# V3.net
KiCad netlist of a schematic drawn in Altium Designer
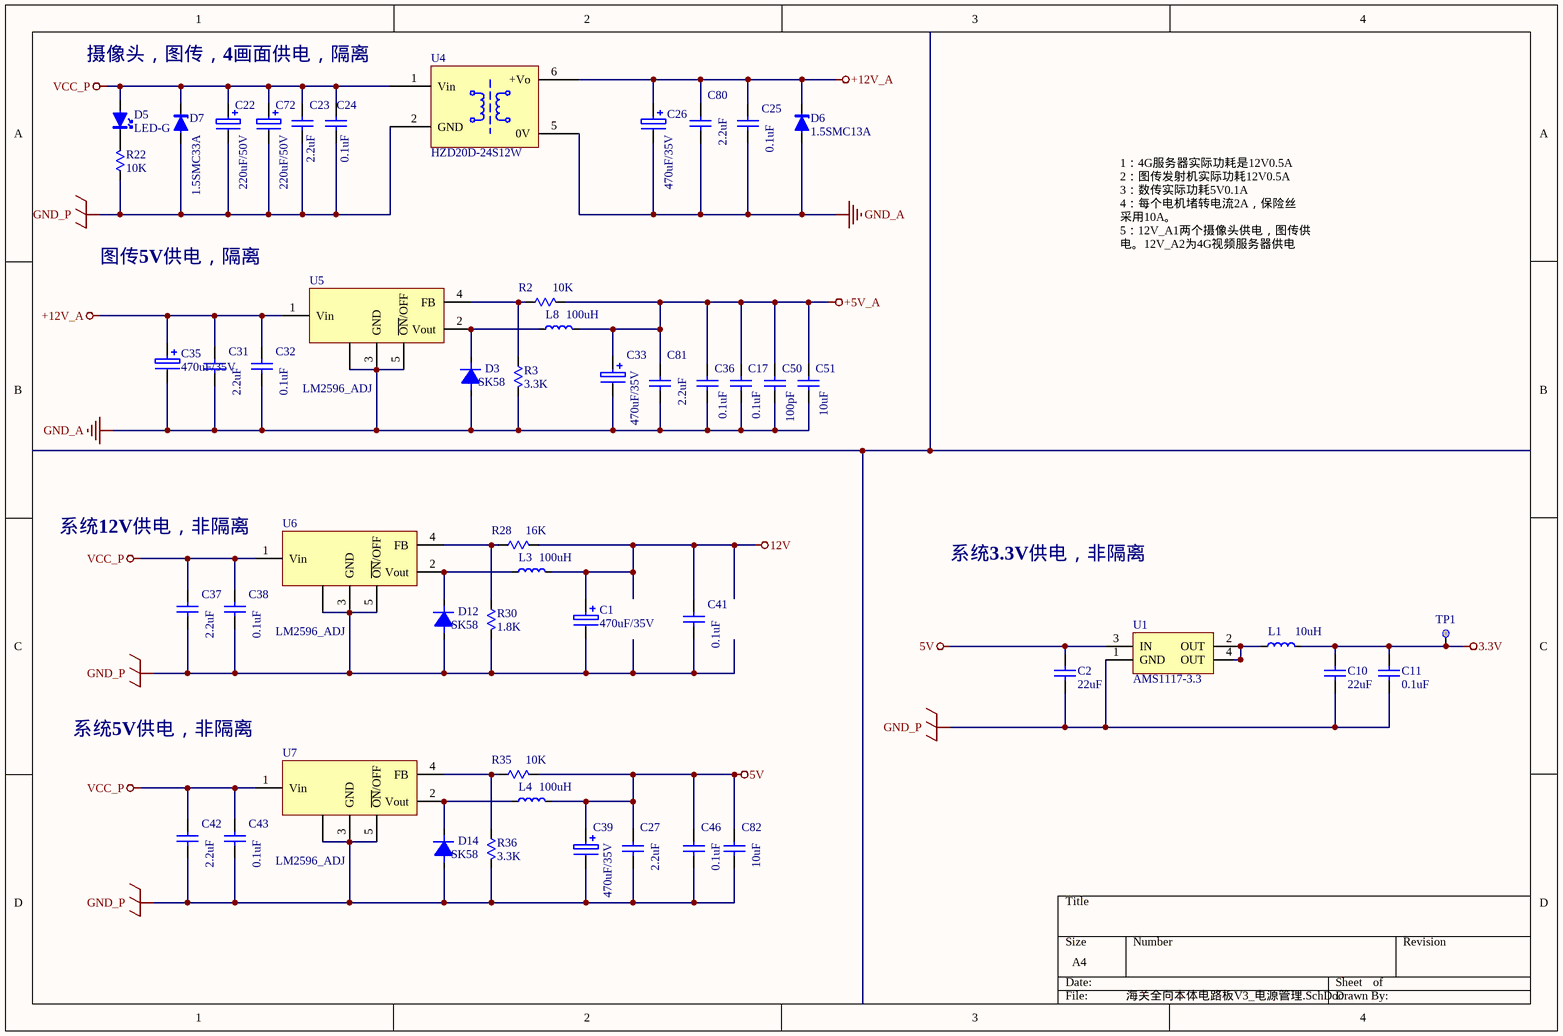
[diagram p0: 海关全向本体电路板V3_电源管理.SchDoc]

(export (version "E")
  (design (tool "Eeschema 10.0.6"))
  (components
    (comp (ref "C1")
      (value "470uF/35V")
      (footprint "CAPPR-10X10-SM")
      (description "Electrolytic Capacitor")
      (libsource (lib "*") (part "ELECTRO"))
    )
    (comp (ref "C2")
      (value "22uF")
      (footprint "C1206-S")
      (description "CAP")
      (fields (field (name "PUBLISHER") "Altium Limited"))
      (libsource (lib "Passive Components Class") (part "CAP"))
    )
    (comp (ref "C10")
      (value "22uF")
      (footprint "C1206-S")
      (description "CAP")
      (fields (field (name "PUBLISHER") "Altium Limited"))
      (libsource (lib "Passive Components Class") (part "CAP"))
    )
    (comp (ref "C11")
      (value "0.1uF")
      (footprint "C0603-S")
      (description "CAP")
      (fields (field (name "PUBLISHER") "Altium Limited"))
      (libsource (lib "Passive Components Class") (part "CAP"))
    )
    (comp (ref "C17")
      (value "0.1uF")
      (footprint "C0603-S")
      (description "CAP")
      (fields (field (name "PUBLISHER") "Altium Limited"))
      (libsource (lib "Passive Components Class") (part "CAP"))
    )
    (comp (ref "C22")
      (value "220uF/50V")
      (footprint "CAPPR-10X10-SM")
      (description "Electrolytic Capacitor")
      (libsource (lib "*") (part "ELECTRO"))
    )
    (comp (ref "C23")
      (value "2.2uF")
      (footprint "C1210-S")
      (description "CAP")
      (fields (field (name "PUBLISHER") "Altium Limited"))
      (libsource (lib "Passive Components Class") (part "CAP"))
    )
    (comp (ref "C24")
      (value "0.1uF")
      (footprint "C0603-S")
      (description "CAP")
      (fields (field (name "PUBLISHER") "Altium Limited"))
      (libsource (lib "Passive Components Class") (part "CAP"))
    )
    (comp (ref "C25")
      (value "0.1uF")
      (footprint "C0603-S")
      (description "CAP")
      (fields (field (name "PUBLISHER") "Altium Limited"))
      (libsource (lib "Passive Components Class") (part "CAP"))
    )
    (comp (ref "C26")
      (value "470uF/35V")
      (footprint "CAPPR-10X10-SM")
      (description "Electrolytic Capacitor")
      (libsource (lib "*") (part "ELECTRO"))
    )
    (comp (ref "C27")
      (value "2.2uF")
      (footprint "C1210-S")
      (description "CAP")
      (fields (field (name "PUBLISHER") "Altium Limited"))
      (libsource (lib "Passive Components Class") (part "CAP"))
    )
    (comp (ref "C31")
      (value "2.2uF")
      (footprint "C1210-S")
      (description "CAP")
      (fields (field (name "PUBLISHER") "Altium Limited"))
      (libsource (lib "Passive Components Class") (part "CAP"))
    )
    (comp (ref "C32")
      (value "0.1uF")
      (footprint "C0603-S")
      (description "CAP")
      (fields (field (name "PUBLISHER") "Altium Limited"))
      (libsource (lib "Passive Components Class") (part "CAP"))
    )
    (comp (ref "C33")
      (value "470uF/35V")
      (footprint "CAPPR-10X10-SM")
      (description "Electrolytic Capacitor")
      (libsource (lib "*") (part "ELECTRO"))
    )
    (comp (ref "C35")
      (value "470uF/35V")
      (footprint "CAPPR-10X10-SM")
      (description "Electrolytic Capacitor")
      (libsource (lib "*") (part "ELECTRO"))
    )
    (comp (ref "C36")
      (value "0.1uF")
      (footprint "C0603-S")
      (description "CAP")
      (fields (field (name "PUBLISHER") "Altium Limited"))
      (libsource (lib "Passive Components Class") (part "CAP"))
    )
    (comp (ref "C37")
      (value "2.2uF")
      (footprint "C1210-S")
      (description "CAP")
      (fields (field (name "PUBLISHER") "Altium Limited"))
      (libsource (lib "Passive Components Class") (part "CAP"))
    )
    (comp (ref "C38")
      (value "0.1uF")
      (footprint "C0603-S")
      (description "CAP")
      (fields (field (name "PUBLISHER") "Altium Limited"))
      (libsource (lib "Passive Components Class") (part "CAP"))
    )
    (comp (ref "C39")
      (value "470uF/35V")
      (footprint "CAPPR-10X10-SM")
      (description "Electrolytic Capacitor")
      (libsource (lib "*") (part "ELECTRO"))
    )
    (comp (ref "C41")
      (value "0.1uF")
      (footprint "C0603-S")
      (description "CAP")
      (fields (field (name "PUBLISHER") "Altium Limited"))
      (libsource (lib "Passive Components Class") (part "CAP"))
    )
    (comp (ref "C42")
      (value "2.2uF")
      (footprint "C1210-S")
      (description "CAP")
      (fields (field (name "PUBLISHER") "Altium Limited"))
      (libsource (lib "Passive Components Class") (part "CAP"))
    )
    (comp (ref "C43")
      (value "0.1uF")
      (footprint "C0603-S")
      (description "CAP")
      (fields (field (name "PUBLISHER") "Altium Limited"))
      (libsource (lib "Passive Components Class") (part "CAP"))
    )
    (comp (ref "C46")
      (value "0.1uF")
      (footprint "C0603-S")
      (description "CAP")
      (fields (field (name "PUBLISHER") "Altium Limited"))
      (libsource (lib "Passive Components Class") (part "CAP"))
    )
    (comp (ref "C50")
      (value "100pF")
      (footprint "C0603-S")
      (description "CAP")
      (fields (field (name "PUBLISHER") "Altium Limited"))
      (libsource (lib "Passive Components Class") (part "CAP"))
    )
    (comp (ref "C51")
      (value "10uF")
      (footprint "C0603-S")
      (description "CAP")
      (fields (field (name "PUBLISHER") "Altium Limited"))
      (libsource (lib "Passive Components Class") (part "CAP"))
    )
    (comp (ref "C72")
      (value "220uF/50V")
      (footprint "CAPPR-10X10-SM")
      (description "Electrolytic Capacitor")
      (libsource (lib "*") (part "ELECTRO"))
    )
    (comp (ref "C80")
      (value "2.2uF")
      (footprint "C1210-S")
      (description "CAP")
      (fields (field (name "PUBLISHER") "Altium Limited"))
      (libsource (lib "Passive Components Class") (part "CAP"))
    )
    (comp (ref "C81")
      (value "2.2uF")
      (footprint "C1210-S")
      (description "CAP")
      (fields (field (name "PUBLISHER") "Altium Limited"))
      (libsource (lib "Passive Components Class") (part "CAP"))
    )
    (comp (ref "C82")
      (value "10uF")
      (footprint "C0603-S")
      (description "CAP")
      (fields (field (name "PUBLISHER") "Altium Limited"))
      (libsource (lib "Passive Components Class") (part "CAP"))
    )
    (comp (ref "D3")
      (value "SK58")
      (footprint "SMB-S")
      (description "Diode")
      (libsource (lib "*") (part "DIODE1"))
    )
    (comp (ref "D5")
      (value "LED-G")
      (footprint "LED0805-S")
      (libsource (lib "Passive Components Class") (part "LED"))
    )
    (comp (ref "D6")
      (value "1.5SMC13A")
      (footprint "SMC-S")
      (description "Small Signal Zener Diodes")
      (libsource (lib "Passive Components Class") (part "DIODE-ZENER"))
    )
    (comp (ref "D7")
      (value "1.5SMC33A")
      (footprint "SMC-S")
      (description "Small Signal Zener Diodes")
      (libsource (lib "Passive Components Class") (part "DIODE-ZENER"))
    )
    (comp (ref "D12")
      (value "SK58")
      (footprint "SMB-S")
      (description "Diode")
      (libsource (lib "*") (part "DIODE1"))
    )
    (comp (ref "D14")
      (value "SK58")
      (footprint "SMB-S")
      (description "Diode")
      (libsource (lib "*") (part "DIODE1"))
    )
    (comp (ref "L1")
      (value "10uH")
      (footprint "L0805-C")
      (description "INDUCTOR")
      (fields (field (name "PUBLISHER") "Altium Limited"))
      (libsource (lib "Passive Components Class") (part "INDUCTOR"))
    )
    (comp (ref "L3")
      (value "100uH")
      (footprint "L5050-P")
      (description "INDUCTOR")
      (fields (field (name "PUBLISHER") "Altium Limited"))
      (libsource (lib "Passive Components Class") (part "INDUCTOR"))
    )
    (comp (ref "L4")
      (value "100uH")
      (footprint "L5050-P")
      (description "INDUCTOR")
      (fields (field (name "PUBLISHER") "Altium Limited"))
      (libsource (lib "Passive Components Class") (part "INDUCTOR"))
    )
    (comp (ref "L8")
      (value "100uH")
      (footprint "L5050-P")
      (description "INDUCTOR")
      (fields (field (name "PUBLISHER") "Altium Limited"))
      (libsource (lib "Passive Components Class") (part "INDUCTOR"))
    )
    (comp (ref "R2")
      (value "10K")
      (footprint "R0805-S")
      (description "Resistor")
      (fields (field (name "PUBLISHER") "Altium Limited"))
      (libsource (lib "Passive Components Class") (part "RES"))
    )
    (comp (ref "R3")
      (value "3.3K")
      (footprint "R0805-S")
      (description "Resistor")
      (fields (field (name "PUBLISHER") "Altium Limited"))
      (libsource (lib "Passive Components Class") (part "RES"))
    )
    (comp (ref "R22")
      (value "10K")
      (footprint "R0805-S")
      (description "Resistor")
      (fields (field (name "PUBLISHER") "Altium Limited"))
      (libsource (lib "UP-Robot") (part "Res"))
    )
    (comp (ref "R28")
      (value "16K")
      (footprint "R0805-S")
      (description "Resistor")
      (fields (field (name "PUBLISHER") "Altium Limited"))
      (libsource (lib "Passive Components Class") (part "RES"))
    )
    (comp (ref "R30")
      (value "1.8K")
      (footprint "R0805-S")
      (description "Resistor")
      (fields (field (name "PUBLISHER") "Altium Limited"))
      (libsource (lib "Passive Components Class") (part "RES"))
    )
    (comp (ref "R35")
      (value "10K")
      (footprint "R0805-S")
      (description "Resistor")
      (fields (field (name "PUBLISHER") "Altium Limited"))
      (libsource (lib "Passive Components Class") (part "RES"))
    )
    (comp (ref "R36")
      (value "3.3K")
      (footprint "R0805-S")
      (description "Resistor")
      (fields (field (name "PUBLISHER") "Altium Limited"))
      (libsource (lib "Passive Components Class") (part "RES"))
    )
    (comp (ref "TP1")
      (value "TestPoint")
      (footprint "MARK-S")
      (libsource (lib "Connector Class") (part "TestPoint"))
    )
    (comp (ref "U1")
      (value "AMS1117-3.3")
      (footprint "SOT-223")
      (description "800mA and 1A Low Dropout Positive Regulator 2.85V, 3.3V, 5V, and Adjustable")
      (fields (field (name "PUBLISHER") "Altium Limited"))
      (libsource (lib "BB Power Mgt Voltage Regulator") (part "REG1117-3.3"))
    )
    (comp (ref "U4")
      (value "HZD20D-24S12W")
      (footprint "HZD20D-24S12W")
      (libsource (lib "Productor Class") (part "HZD20D-24S12W"))
    )
    (comp (ref "U5") (value "LM2596_ADJ") (footprint "TO263") (libsource (lib "*") (part "LM2575")))
    (comp (ref "U6") (value "LM2596_ADJ") (footprint "TO263") (libsource (lib "*") (part "LM2575")))
    (comp (ref "U7") (value "LM2596_ADJ") (footprint "TO263") (libsource (lib "*") (part "LM2575")))
  )
  (nets
    (net (code "1") (name "+5V_A") (class "Default")
      (node (ref "C17") (pin "2") (pinfunction "2_2") (pintype "passive"))
      (node (ref "C33") (pin "1") (pinfunction "1_1") (pintype "passive"))
      (node (ref "C36") (pin "2") (pinfunction "2_2") (pintype "passive"))
      (node (ref "C50") (pin "2") (pinfunction "2_2") (pintype "passive"))
      (node (ref "C51") (pin "2") (pinfunction "2_2") (pintype "passive"))
      (node (ref "C81") (pin "2") (pinfunction "2_2") (pintype "passive"))
      (node (ref "L8") (pin "1") (pinfunction "1_1") (pintype "passive"))
      (node (ref "R2") (pin "1") (pinfunction "1_1") (pintype "passive"))
    )
    (net (code "2") (name "+12V_A") (class "Default")
      (node (ref "C25") (pin "2") (pinfunction "2_2") (pintype "passive"))
      (node (ref "C26") (pin "1") (pinfunction "1_1") (pintype "passive"))
      (node (ref "C31") (pin "2") (pinfunction "2_2") (pintype "passive"))
      (node (ref "C32") (pin "2") (pinfunction "2_2") (pintype "passive"))
      (node (ref "C35") (pin "1") (pinfunction "1_1") (pintype "passive"))
      (node (ref "C80") (pin "2") (pinfunction "2_2") (pintype "passive"))
      (node (ref "D6") (pin "2") (pinfunction "K_2") (pintype "passive"))
      (node (ref "U4") (pin "6") (pinfunction "+Vo_6") (pintype "passive"))
      (node (ref "U5") (pin "1") (pinfunction "Vin_1") (pintype "power_in"))
    )
    (net (code "3") (name "3.3V") (class "Default")
      (node (ref "C10") (pin "1") (pinfunction "1_1") (pintype "passive"))
      (node (ref "C11") (pin "2") (pinfunction "2_2") (pintype "passive"))
      (node (ref "L1") (pin "1") (pinfunction "1_1") (pintype "passive"))
      (node (ref "TP1") (pin "1") (pinfunction "1_1") (pintype "passive"))
    )
    (net (code "4") (name "5V") (class "Default")
      (node (ref "C2") (pin "1") (pinfunction "1_1") (pintype "passive"))
      (node (ref "C27") (pin "2") (pinfunction "2_2") (pintype "passive"))
      (node (ref "C39") (pin "1") (pinfunction "1_1") (pintype "passive"))
      (node (ref "C46") (pin "2") (pinfunction "2_2") (pintype "passive"))
      (node (ref "C82") (pin "2") (pinfunction "2_2") (pintype "passive"))
      (node (ref "L4") (pin "1") (pinfunction "1_1") (pintype "passive"))
      (node (ref "R35") (pin "1") (pinfunction "1_1") (pintype "passive"))
      (node (ref "U1") (pin "3") (pinfunction "IN_3") (pintype "power_in"))
    )
    (net (code "5") (name "12V") (class "Default")
      (node (ref "C1") (pin "1") (pinfunction "1_1") (pintype "passive"))
      (node (ref "C41") (pin "2") (pinfunction "2_2") (pintype "passive"))
      (node (ref "L3") (pin "1") (pinfunction "1_1") (pintype "passive"))
      (node (ref "R28") (pin "1") (pinfunction "1_1") (pintype "passive"))
    )
    (net (code "6") (name "GND_A") (class "Default")
      (node (ref "C17") (pin "1") (pinfunction "1_1") (pintype "passive"))
      (node (ref "C25") (pin "1") (pinfunction "1_1") (pintype "passive"))
      (node (ref "C26") (pin "2") (pinfunction "2_2") (pintype "passive"))
      (node (ref "C31") (pin "1") (pinfunction "1_1") (pintype "passive"))
      (node (ref "C32") (pin "1") (pinfunction "1_1") (pintype "passive"))
      (node (ref "C33") (pin "2") (pinfunction "2_2") (pintype "passive"))
      (node (ref "C35") (pin "2") (pinfunction "2_2") (pintype "passive"))
      (node (ref "C36") (pin "1") (pinfunction "1_1") (pintype "passive"))
      (node (ref "C50") (pin "1") (pinfunction "1_1") (pintype "passive"))
      (node (ref "C51") (pin "1") (pinfunction "1_1") (pintype "passive"))
      (node (ref "C80") (pin "1") (pinfunction "1_1") (pintype "passive"))
      (node (ref "C81") (pin "1") (pinfunction "1_1") (pintype "passive"))
      (node (ref "D3") (pin "1") (pinfunction "A_1") (pintype "passive"))
      (node (ref "D6") (pin "1") (pinfunction "A_1") (pintype "passive"))
      (node (ref "R3") (pin "1") (pinfunction "1_1") (pintype "passive"))
      (node (ref "U4") (pin "5") (pinfunction "0V_5") (pintype "passive"))
      (node (ref "U5") (pin "0") (pinfunction "GND_0") (pintype "passive"))
      (node (ref "U5") (pin "3") (pinfunction "GND_3") (pintype "power_in"))
      (node (ref "U5") (pin "5") (pinfunction "~{ON}/OFF_5") (pintype "passive"))
    )
    (net (code "7") (name "GND_P") (class "Default")
      (node (ref "C1") (pin "2") (pinfunction "2_2") (pintype "passive"))
      (node (ref "C10") (pin "2") (pinfunction "2_2") (pintype "passive"))
      (node (ref "C11") (pin "1") (pinfunction "1_1") (pintype "passive"))
      (node (ref "C2") (pin "2") (pinfunction "2_2") (pintype "passive"))
      (node (ref "C22") (pin "2") (pinfunction "2_2") (pintype "passive"))
      (node (ref "C23") (pin "1") (pinfunction "1_1") (pintype "passive"))
      (node (ref "C24") (pin "1") (pinfunction "1_1") (pintype "passive"))
      (node (ref "C27") (pin "1") (pinfunction "1_1") (pintype "passive"))
      (node (ref "C37") (pin "1") (pinfunction "1_1") (pintype "passive"))
      (node (ref "C38") (pin "1") (pinfunction "1_1") (pintype "passive"))
      (node (ref "C39") (pin "2") (pinfunction "2_2") (pintype "passive"))
      (node (ref "C41") (pin "1") (pinfunction "1_1") (pintype "passive"))
      (node (ref "C42") (pin "1") (pinfunction "1_1") (pintype "passive"))
      (node (ref "C43") (pin "1") (pinfunction "1_1") (pintype "passive"))
      (node (ref "C46") (pin "1") (pinfunction "1_1") (pintype "passive"))
      (node (ref "C72") (pin "2") (pinfunction "2_2") (pintype "passive"))
      (node (ref "C82") (pin "1") (pinfunction "1_1") (pintype "passive"))
      (node (ref "D12") (pin "1") (pinfunction "A_1") (pintype "passive"))
      (node (ref "D14") (pin "1") (pinfunction "A_1") (pintype "passive"))
      (node (ref "D7") (pin "1") (pinfunction "A_1") (pintype "passive"))
      (node (ref "R22") (pin "2") (pinfunction "2_2") (pintype "passive"))
      (node (ref "R30") (pin "1") (pinfunction "1_1") (pintype "passive"))
      (node (ref "R36") (pin "1") (pinfunction "1_1") (pintype "passive"))
      (node (ref "U1") (pin "1") (pinfunction "GND_1") (pintype "power_in"))
      (node (ref "U4") (pin "2") (pinfunction "GND_2") (pintype "passive"))
      (node (ref "U6") (pin "0") (pinfunction "GND_0") (pintype "passive"))
      (node (ref "U6") (pin "3") (pinfunction "GND_3") (pintype "power_in"))
      (node (ref "U6") (pin "5") (pinfunction "~{ON}/OFF_5") (pintype "passive"))
      (node (ref "U7") (pin "0") (pinfunction "GND_0") (pintype "passive"))
      (node (ref "U7") (pin "3") (pinfunction "GND_3") (pintype "power_in"))
      (node (ref "U7") (pin "5") (pinfunction "~{ON}/OFF_5") (pintype "passive"))
    )
    (net (code "8") (name "Net-(D3-K)") (class "Default")
      (node (ref "D3") (pin "2") (pinfunction "K_2") (pintype "passive"))
      (node (ref "L8") (pin "2") (pinfunction "2_2") (pintype "passive"))
      (node (ref "U5") (pin "2") (pinfunction "Vout_2") (pintype "power_in"))
    )
    (net (code "9") (name "Net-(D5-K)") (class "Default")
      (node (ref "D5") (pin "2") (pinfunction "K_2") (pintype "passive"))
      (node (ref "R22") (pin "1") (pinfunction "1_1") (pintype "passive"))
    )
    (net (code "10") (name "Net-(D12-K)") (class "Default")
      (node (ref "D12") (pin "2") (pinfunction "K_2") (pintype "passive"))
      (node (ref "L3") (pin "2") (pinfunction "2_2") (pintype "passive"))
      (node (ref "U6") (pin "2") (pinfunction "Vout_2") (pintype "power_in"))
    )
    (net (code "11") (name "Net-(D14-K)") (class "Default")
      (node (ref "D14") (pin "2") (pinfunction "K_2") (pintype "passive"))
      (node (ref "L4") (pin "2") (pinfunction "2_2") (pintype "passive"))
      (node (ref "U7") (pin "2") (pinfunction "Vout_2") (pintype "power_in"))
    )
    (net (code "12") (name "Net-(L1-Pad2)") (class "Default")
      (node (ref "L1") (pin "2") (pinfunction "2_2") (pintype "passive"))
      (node (ref "U1") (pin "2") (pinfunction "OUT_2") (pintype "power_in"))
      (node (ref "U1") (pin "4") (pinfunction "OUT_4") (pintype "power_in"))
    )
    (net (code "13") (name "Net-(U5-FB)") (class "Default")
      (node (ref "R2") (pin "2") (pinfunction "2_2") (pintype "passive"))
      (node (ref "R3") (pin "2") (pinfunction "2_2") (pintype "passive"))
      (node (ref "U5") (pin "4") (pinfunction "FB_4") (pintype "passive"))
    )
    (net (code "14") (name "Net-(U6-FB)") (class "Default")
      (node (ref "R28") (pin "2") (pinfunction "2_2") (pintype "passive"))
      (node (ref "R30") (pin "2") (pinfunction "2_2") (pintype "passive"))
      (node (ref "U6") (pin "4") (pinfunction "FB_4") (pintype "passive"))
    )
    (net (code "15") (name "Net-(U7-FB)") (class "Default")
      (node (ref "R35") (pin "2") (pinfunction "2_2") (pintype "passive"))
      (node (ref "R36") (pin "2") (pinfunction "2_2") (pintype "passive"))
      (node (ref "U7") (pin "4") (pinfunction "FB_4") (pintype "passive"))
    )
    (net (code "16") (name "VCC_P") (class "Default")
      (node (ref "C22") (pin "1") (pinfunction "1_1") (pintype "passive"))
      (node (ref "C23") (pin "2") (pinfunction "2_2") (pintype "passive"))
      (node (ref "C24") (pin "2") (pinfunction "2_2") (pintype "passive"))
      (node (ref "C37") (pin "2") (pinfunction "2_2") (pintype "passive"))
      (node (ref "C38") (pin "2") (pinfunction "2_2") (pintype "passive"))
      (node (ref "C42") (pin "2") (pinfunction "2_2") (pintype "passive"))
      (node (ref "C43") (pin "2") (pinfunction "2_2") (pintype "passive"))
      (node (ref "C72") (pin "1") (pinfunction "1_1") (pintype "passive"))
      (node (ref "D5") (pin "1") (pinfunction "A_1") (pintype "passive"))
      (node (ref "D7") (pin "2") (pinfunction "K_2") (pintype "passive"))
      (node (ref "U4") (pin "1") (pinfunction "Vin_1") (pintype "passive"))
      (node (ref "U6") (pin "1") (pinfunction "Vin_1") (pintype "power_in"))
      (node (ref "U7") (pin "1") (pinfunction "Vin_1") (pintype "power_in"))
    )
  )
)
